# V3.net
KiCad netlist of a schematic drawn in Altium Designer
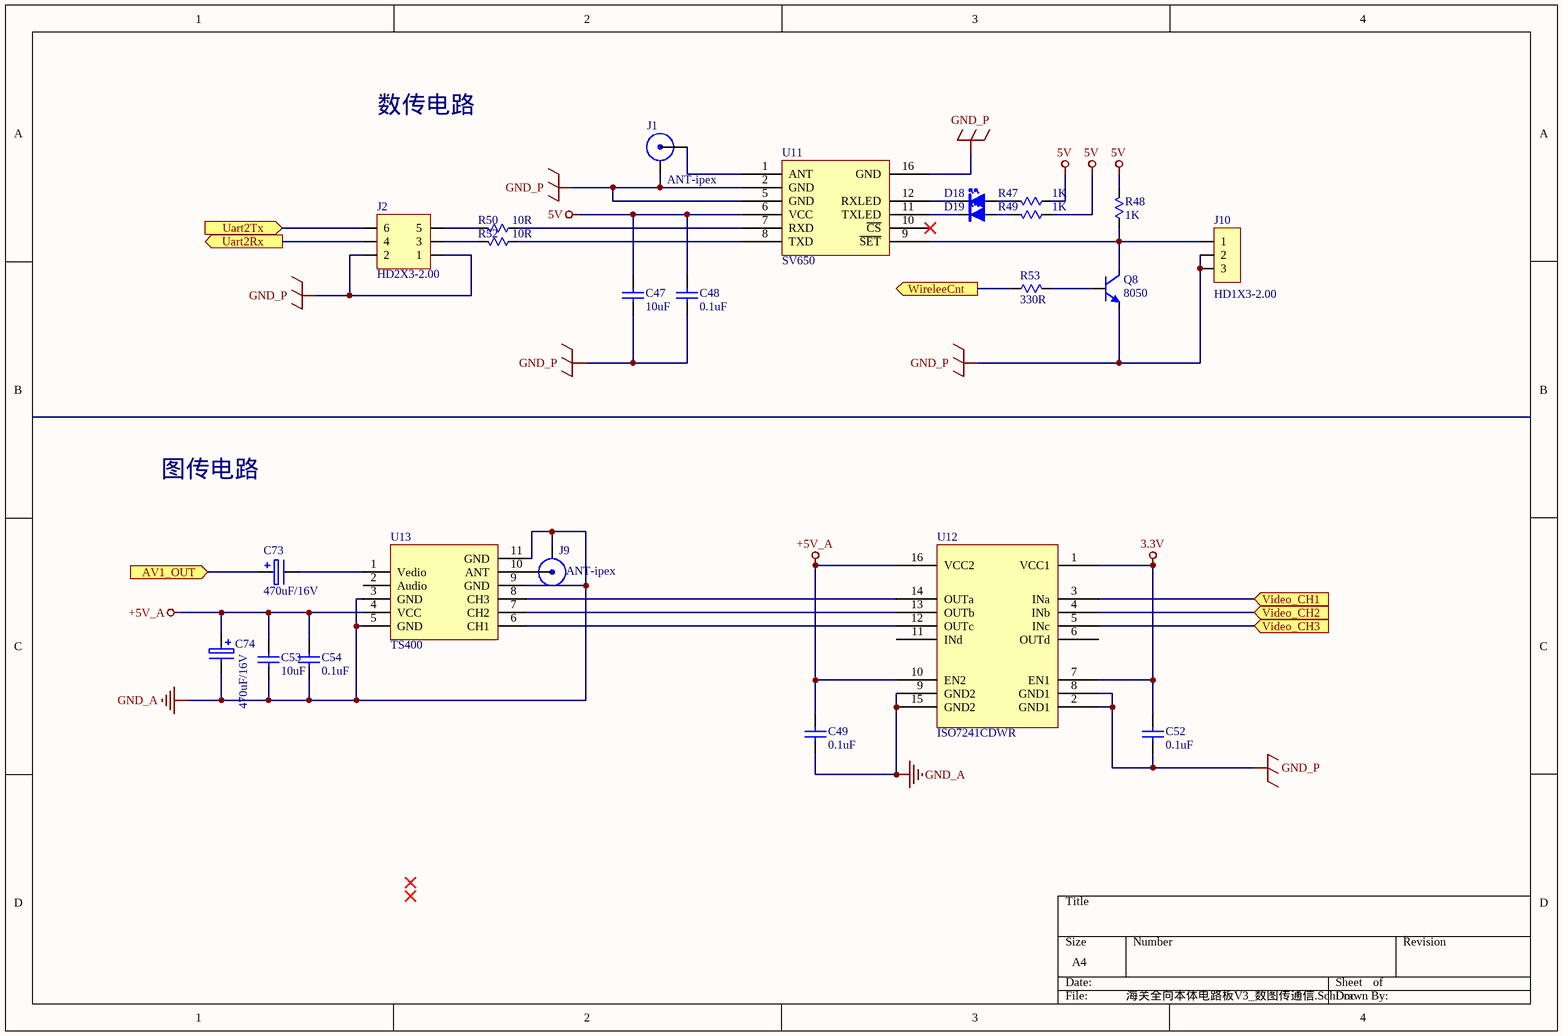
[diagram p0: 海关全向本体电路板V3_数图传通信.SchDoc]

(export (version "E")
  (design (tool "Eeschema 10.0.6"))
  (components
    (comp (ref "C47") (value "10uF") (footprint "C0603-S") (libsource (lib "SMD") (part "Cap Semi")))
    (comp (ref "C48") (value "0.1uF") (footprint "C0603-S") (libsource (lib "SMD") (part "Cap Semi")))
    (comp (ref "C49") (value "0.1uF") (footprint "C0603-S") (libsource (lib "SMD") (part "Cap Semi")))
    (comp (ref "C52") (value "0.1uF") (footprint "C0603-S") (libsource (lib "SMD") (part "Cap Semi")))
    (comp (ref "C53") (value "10uF") (footprint "C0603-S") (libsource (lib "SMD") (part "Cap Semi")))
    (comp (ref "C54") (value "0.1uF") (footprint "C0603-S") (libsource (lib "SMD") (part "Cap Semi")))
    (comp (ref "C73")
      (value "470uF/16V")
      (footprint "CAPPR-8X10-SM")
      (description "Electrolytic Capacitor")
      (libsource (lib "*") (part "ELECTRO"))
    )
    (comp (ref "C74")
      (value "470uF/16V")
      (footprint "CAPPR-8X10-SM")
      (description "Electrolytic Capacitor")
      (libsource (lib "*") (part "ELECTRO"))
    )
    (comp (ref "D18")
      (value "LED")
      (footprint "LED0603")
      (libsource (lib "Passive Components Class") (part "LED"))
    )
    (comp (ref "D19")
      (value "LED")
      (footprint "LED0603")
      (libsource (lib "Passive Components Class") (part "LED"))
    )
    (comp (ref "J1") (value "ANT-ipex") (footprint "SMJB-5.00") (libsource (lib "RLCYDF") (part "ANT-ipex")))
    (comp (ref "J2")
      (value "HD2X3-2.00")
      (footprint "HD2X3-2.00")
      (libsource (lib "Connector Class") (part "HEADER2X3-2.0"))
    )
    (comp (ref "J9") (value "ANT-ipex") (footprint "SMJB-5.00") (libsource (lib "RLCYDF") (part "ANT-ipex")))
    (comp (ref "J10")
      (value "HD1X3-2.00")
      (footprint "HD1X3-2.00")
      (libsource (lib "Connector Class") (part "HEADER1X3"))
    )
    (comp (ref "Q8")
      (value "8050")
      (footprint "SOT-23")
      (description "NPN General Purpose Amplifier")
      (fields (field (name "PUBLISHER") "Altium Limited"))
      (libsource (lib "Bdmc4810") (part "NPN"))
    )
    (comp (ref "R47")
      (value "1K")
      (footprint "R0603-S")
      (description "Resistor")
      (fields (field (name "PUBLISHER") "Altium Limited"))
      (libsource (lib "UP-Robot") (part "Res"))
    )
    (comp (ref "R48")
      (value "1K")
      (footprint "R0603-S")
      (description "Resistor")
      (fields (field (name "PUBLISHER") "Altium Limited"))
      (libsource (lib "Passive Components Class") (part "RES"))
    )
    (comp (ref "R49")
      (value "1K")
      (footprint "R0603-S")
      (description "Resistor")
      (fields (field (name "PUBLISHER") "Altium Limited"))
      (libsource (lib "UP-Robot") (part "Res"))
    )
    (comp (ref "R50")
      (value "10R")
      (footprint "R0603-S")
      (description "Resistor")
      (fields (field (name "PUBLISHER") "Altium Limited"))
      (libsource (lib "UP-Robot") (part "Res"))
    )
    (comp (ref "R52")
      (value "10R")
      (footprint "R0603-S")
      (description "Resistor")
      (fields (field (name "PUBLISHER") "Altium Limited"))
      (libsource (lib "UP-Robot") (part "Res"))
    )
    (comp (ref "R53")
      (value "330R")
      (footprint "R0603-S")
      (description "Resistor")
      (fields (field (name "PUBLISHER") "Altium Limited"))
      (libsource (lib "Passive Components Class") (part "RES"))
    )
    (comp (ref "U11") (value "SV650") (footprint "SV650") (libsource (lib "Module") (part "SV650")))
    (comp (ref "U12")
      (value "ISO7241CDWR")
      (footprint "SO16-290")
      (description "Octal bus transceiver and 3.3V to 5V shifter with 3-state outputs")
      (libsource (lib "Logic Class") (part "ISO7241A"))
    )
    (comp (ref "U13") (value "TS400") (footprint "TS400") (libsource (lib "Productor Class") (part "TS400")))
  )
  (nets
    (net (code "1") (name "+5V_A") (class "Default")
      (node (ref "C49") (pin "2") (pinfunction "2_2") (pintype "passive"))
      (node (ref "C53") (pin "2") (pinfunction "2_2") (pintype "passive"))
      (node (ref "C54") (pin "2") (pinfunction "2_2") (pintype "passive"))
      (node (ref "C74") (pin "1") (pinfunction "1_1") (pintype "passive"))
      (node (ref "U12") (pin "10") (pinfunction "EN2_10") (pintype "passive"))
      (node (ref "U12") (pin "16") (pinfunction "VCC2_16") (pintype "passive"))
      (node (ref "U13") (pin "4") (pinfunction "VCC_4") (pintype "passive"))
    )
    (net (code "2") (name "/AV1_OUT") (class "Default")
      (node (ref "C73") (pin "1") (pinfunction "1_1") (pintype "passive"))
    )
    (net (code "3") (name "/Uart2Rx") (class "Default")
      (node (ref "J2") (pin "4") (pinfunction "4_4") (pintype "passive"))
    )
    (net (code "4") (name "/Uart2Tx") (class "Default")
      (node (ref "J2") (pin "6") (pinfunction "6_6") (pintype "passive"))
    )
    (net (code "5") (name "/Video_CH1") (class "Default")
      (node (ref "U12") (pin "3") (pinfunction "INa_3") (pintype "passive"))
    )
    (net (code "6") (name "/Video_CH2") (class "Default")
      (node (ref "U12") (pin "4") (pinfunction "INb_4") (pintype "passive"))
    )
    (net (code "7") (name "/Video_CH3") (class "Default")
      (node (ref "U12") (pin "5") (pinfunction "INc_5") (pintype "passive"))
    )
    (net (code "8") (name "/WireleeCnt") (class "Default")
      (node (ref "R53") (pin "2") (pinfunction "2_2") (pintype "passive"))
    )
    (net (code "9") (name "3.3V") (class "Default")
      (node (ref "C52") (pin "2") (pinfunction "2_2") (pintype "passive"))
      (node (ref "U12") (pin "1") (pinfunction "VCC1_1") (pintype "passive"))
      (node (ref "U12") (pin "7") (pinfunction "EN1_7") (pintype "passive"))
    )
    (net (code "10") (name "5V") (class "Default")
      (node (ref "C47") (pin "2") (pinfunction "2_2") (pintype "passive"))
      (node (ref "C48") (pin "2") (pinfunction "2_2") (pintype "passive"))
      (node (ref "R47") (pin "1") (pinfunction "1_1") (pintype "passive"))
      (node (ref "R48") (pin "1") (pinfunction "1_1") (pintype "passive"))
      (node (ref "R49") (pin "1") (pinfunction "1_1") (pintype "passive"))
      (node (ref "U11") (pin "6") (pinfunction "VCC_6") (pintype "passive"))
    )
    (net (code "11") (name "GND_A") (class "Default")
      (node (ref "C49") (pin "1") (pinfunction "1_1") (pintype "passive"))
      (node (ref "C53") (pin "1") (pinfunction "1_1") (pintype "passive"))
      (node (ref "C54") (pin "1") (pinfunction "1_1") (pintype "passive"))
      (node (ref "C74") (pin "2") (pinfunction "2_2") (pintype "passive"))
      (node (ref "J9") (pin "2") (pinfunction "GND_2") (pintype "passive"))
      (node (ref "U12") (pin "15") (pinfunction "GND2_15") (pintype "passive"))
      (node (ref "U12") (pin "9") (pinfunction "GND2_9") (pintype "passive"))
      (node (ref "U13") (pin "11") (pinfunction "GND_11") (pintype "passive"))
      (node (ref "U13") (pin "3") (pinfunction "GND_3") (pintype "passive"))
      (node (ref "U13") (pin "5") (pinfunction "GND_5") (pintype "passive"))
      (node (ref "U13") (pin "9") (pinfunction "GND_9") (pintype "passive"))
    )
    (net (code "12") (name "GND_P") (class "Default")
      (node (ref "C47") (pin "1") (pinfunction "1_1") (pintype "passive"))
      (node (ref "C48") (pin "1") (pinfunction "1_1") (pintype "passive"))
      (node (ref "C52") (pin "1") (pinfunction "1_1") (pintype "passive"))
      (node (ref "J1") (pin "2") (pinfunction "GND_2") (pintype "passive"))
      (node (ref "J10") (pin "2") (pinfunction "2_2") (pintype "passive"))
      (node (ref "J10") (pin "3") (pinfunction "3_3") (pintype "passive"))
      (node (ref "J2") (pin "1") (pinfunction "1_1") (pintype "passive"))
      (node (ref "J2") (pin "2") (pinfunction "2_2") (pintype "passive"))
      (node (ref "Q8") (pin "2") (pinfunction "E_2") (pintype "passive"))
      (node (ref "U11") (pin "16") (pinfunction "GND_16") (pintype "passive"))
      (node (ref "U11") (pin "2") (pinfunction "GND_2") (pintype "passive"))
      (node (ref "U11") (pin "5") (pinfunction "GND_5") (pintype "passive"))
      (node (ref "U12") (pin "2") (pinfunction "GND1_2") (pintype "passive"))
      (node (ref "U12") (pin "8") (pinfunction "GND1_8") (pintype "passive"))
    )
    (net (code "13") (name "Net-(D18-A)") (class "Default")
      (node (ref "D18") (pin "1") (pinfunction "A_1") (pintype "passive"))
      (node (ref "R47") (pin "2") (pinfunction "2_2") (pintype "passive"))
    )
    (net (code "14") (name "Net-(D18-K)") (class "Default")
      (node (ref "D18") (pin "2") (pinfunction "K_2") (pintype "passive"))
      (node (ref "U11") (pin "12") (pinfunction "RXLED_12") (pintype "passive"))
    )
    (net (code "15") (name "Net-(D19-A)") (class "Default")
      (node (ref "D19") (pin "1") (pinfunction "A_1") (pintype "passive"))
      (node (ref "R49") (pin "2") (pinfunction "2_2") (pintype "passive"))
    )
    (net (code "16") (name "Net-(D19-K)") (class "Default")
      (node (ref "D19") (pin "2") (pinfunction "K_2") (pintype "passive"))
      (node (ref "U11") (pin "11") (pinfunction "TXLED_11") (pintype "passive"))
    )
    (net (code "17") (name "Net-(J1-ANT)") (class "Default")
      (node (ref "J1") (pin "1") (pinfunction "ANT_1") (pintype "passive"))
      (node (ref "U11") (pin "1") (pinfunction "ANT_1") (pintype "passive"))
    )
    (net (code "18") (name "Net-(J2-Pad3)") (class "Default")
      (node (ref "J2") (pin "3") (pinfunction "3_3") (pintype "passive"))
      (node (ref "R52") (pin "2") (pinfunction "2_2") (pintype "passive"))
    )
    (net (code "19") (name "Net-(J2-Pad5)") (class "Default")
      (node (ref "J2") (pin "5") (pinfunction "5_5") (pintype "passive"))
      (node (ref "R50") (pin "2") (pinfunction "2_2") (pintype "passive"))
    )
    (net (code "20") (name "Net-(J9-ANT)") (class "Default")
      (node (ref "J9") (pin "1") (pinfunction "ANT_1") (pintype "passive"))
      (node (ref "U13") (pin "10") (pinfunction "ANT_10") (pintype "passive"))
    )
    (net (code "21") (name "Net-(Q8-B)") (class "Default")
      (node (ref "Q8") (pin "1") (pinfunction "B_1") (pintype "passive"))
      (node (ref "R53") (pin "1") (pinfunction "1_1") (pintype "passive"))
    )
    (net (code "22") (name "Net-(Q8-C)") (class "Default")
      (node (ref "J10") (pin "1") (pinfunction "1_1") (pintype "passive"))
      (node (ref "Q8") (pin "3") (pinfunction "C_3") (pintype "passive"))
      (node (ref "R48") (pin "2") (pinfunction "2_2") (pintype "passive"))
      (node (ref "U11") (pin "9") (pinfunction "~{SET}_9") (pintype "passive"))
    )
    (net (code "23") (name "Net-(U11-RXD)") (class "Default")
      (node (ref "R50") (pin "1") (pinfunction "1_1") (pintype "passive"))
      (node (ref "U11") (pin "7") (pinfunction "RXD_7") (pintype "passive"))
    )
    (net (code "24") (name "Net-(U11-TXD)") (class "Default")
      (node (ref "R52") (pin "1") (pinfunction "1_1") (pintype "passive"))
      (node (ref "U11") (pin "8") (pinfunction "TXD_8") (pintype "passive"))
    )
    (net (code "25") (name "Net-(U12-OUTa)") (class "Default")
      (node (ref "U12") (pin "14") (pinfunction "OUTa_14") (pintype "passive"))
      (node (ref "U13") (pin "8") (pinfunction "CH3_8") (pintype "passive"))
    )
    (net (code "26") (name "Net-(U12-OUTb)") (class "Default")
      (node (ref "U12") (pin "13") (pinfunction "OUTb_13") (pintype "passive"))
      (node (ref "U13") (pin "7") (pinfunction "CH2_7") (pintype "passive"))
    )
    (net (code "27") (name "Net-(U12-OUTc)") (class "Default")
      (node (ref "U12") (pin "12") (pinfunction "OUTc_12") (pintype "passive"))
      (node (ref "U13") (pin "6") (pinfunction "CH1_6") (pintype "passive"))
    )
    (net (code "28") (name "Net-(U13-Vedio)") (class "Default")
      (node (ref "C73") (pin "2") (pinfunction "2_2") (pintype "passive"))
      (node (ref "U13") (pin "1") (pinfunction "Vedio_1") (pintype "passive"))
    )
    (net (code "29") (name "unconnected-(U11-~{CS}-Pad10)") (class "Default")
      (node (ref "U11") (pin "10") (pinfunction "~{CS}_10") (pintype "passive+no_connect"))
    )
    (net (code "30") (name "unconnected-(U12-INd-Pad11)") (class "Default")
      (node (ref "U12") (pin "11") (pinfunction "INd_11") (pintype "passive"))
    )
    (net (code "31") (name "unconnected-(U12-OUTd-Pad6)") (class "Default")
      (node (ref "U12") (pin "6") (pinfunction "OUTd_6") (pintype "passive"))
    )
    (net (code "32") (name "unconnected-(U13-Audio-Pad2)") (class "Default")
      (node (ref "U13") (pin "2") (pinfunction "Audio_2") (pintype "passive"))
    )
  )
)
